# chainclock.net
KiCad netlist of a schematic drawn in EAGLE
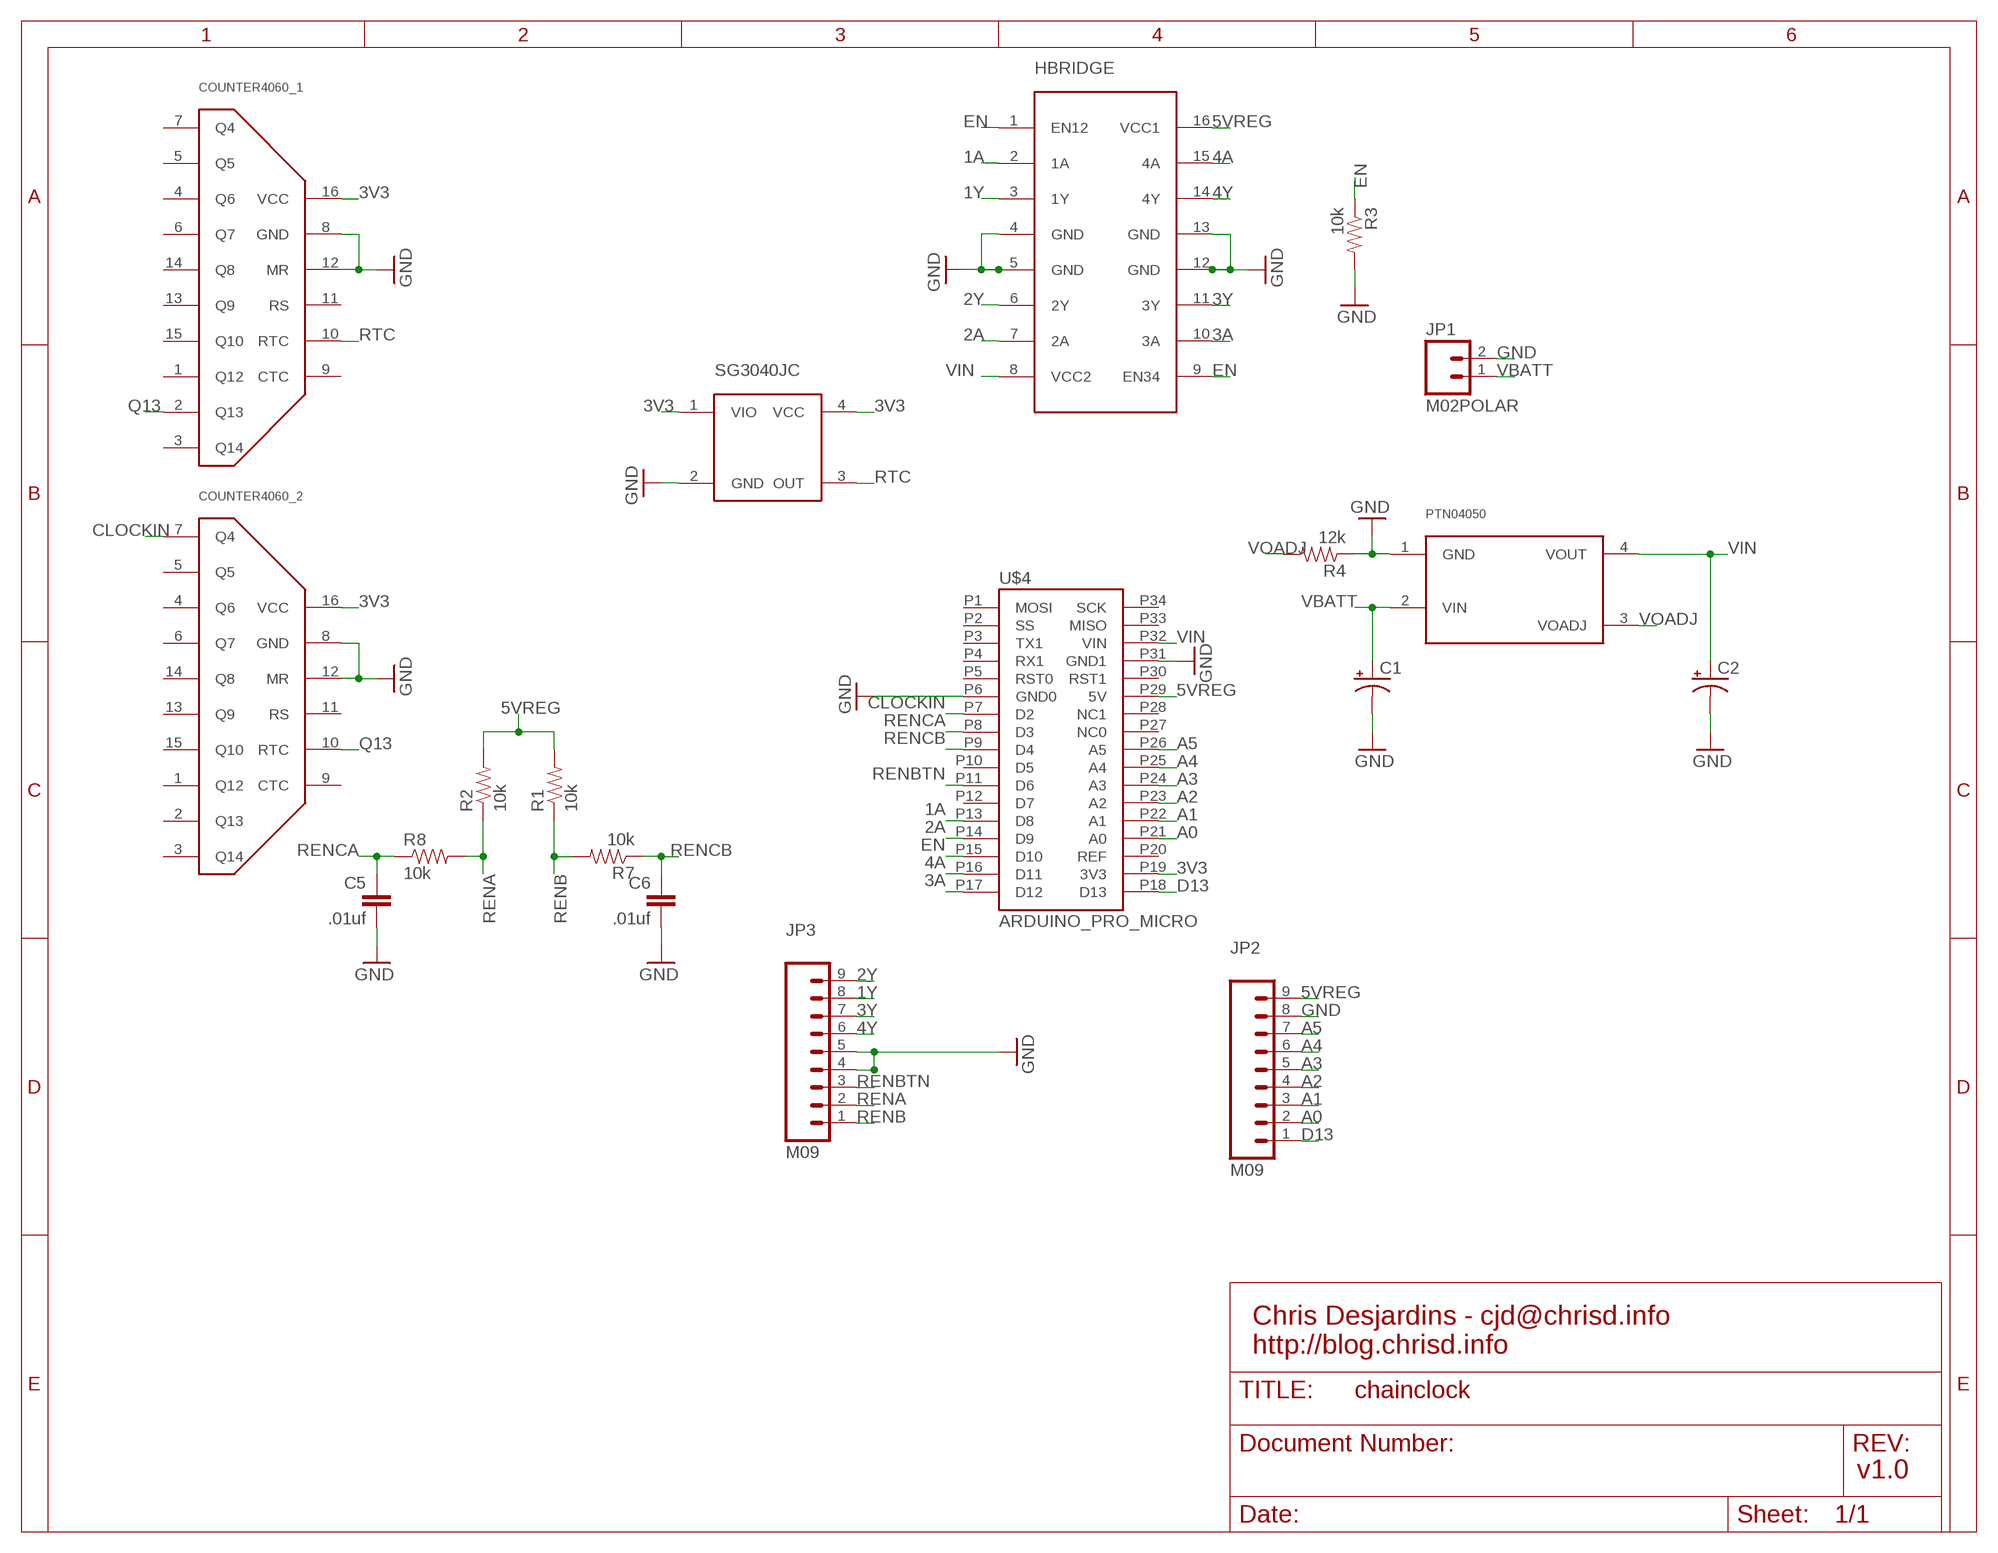
[diagram p0: schematic, sheet 1]

(export (version "E")
  (design (tool "Eeschema 10.0.6"))
  (components
    (comp (ref "C1")
      (value "CAP_POLPTH1")
      (footprint "eagle-import:CPOL-RADIAL-100UF-25V")
      (libsource (lib "eagle-import") (part "CAP_POLPTH1"))
    )
    (comp (ref "C2")
      (value "CAP_POLPTH1")
      (footprint "eagle-import:CPOL-RADIAL-100UF-25V")
      (libsource (lib "eagle-import") (part "CAP_POLPTH1"))
    )
    (comp (ref "C5")
      (value ".01uf")
      (footprint "eagle-import:CAP-PTH-SMALL-KIT")
      (libsource (lib "eagle-import") (part "CAPKIT"))
    )
    (comp (ref "C6")
      (value ".01uf")
      (footprint "eagle-import:CAP-PTH-SMALL-KIT")
      (libsource (lib "eagle-import") (part "CAPKIT"))
    )
    (comp (ref "COUNTER4060_1")
      (value "4060SOIC16")
      (footprint "eagle-import:SO016")
      (libsource (lib "eagle-import") (part "4060SOIC16"))
    )
    (comp (ref "COUNTER4060_2")
      (value "4060SOIC16")
      (footprint "eagle-import:SO016")
      (libsource (lib "eagle-import") (part "4060SOIC16"))
    )
    (comp (ref "HBRIDGE")
      (value "SN754410")
      (footprint "eagle-import:DIL16-KIT")
      (libsource (lib "eagle-import") (part "SN754410"))
    )
    (comp (ref "JP1")
      (value "M02POLAR")
      (footprint "eagle-import:MOLEX-1X2")
      (libsource (lib "eagle-import") (part "M02POLAR"))
    )
    (comp (ref "JP2")
      (value "M09")
      (footprint "eagle-import:1X09")
      (libsource (lib "eagle-import") (part "M09"))
    )
    (comp (ref "JP3")
      (value "M09")
      (footprint "eagle-import:1X09")
      (libsource (lib "eagle-import") (part "M09"))
    )
    (comp (ref "PTN04050")
      (value "PTN0405C")
      (footprint "eagle-import:EUU4")
      (libsource (lib "eagle-import") (part "PTN0405C"))
    )
    (comp (ref "R1")
      (value "10k")
      (footprint "eagle-import:AXIAL-0.3EZ")
      (libsource (lib "eagle-import") (part "RESISTOREZ"))
    )
    (comp (ref "R2")
      (value "10k")
      (footprint "eagle-import:AXIAL-0.3EZ")
      (libsource (lib "eagle-import") (part "RESISTOREZ"))
    )
    (comp (ref "R3")
      (value "10k")
      (footprint "eagle-import:AXIAL-0.3EZ")
      (libsource (lib "eagle-import") (part "RESISTOREZ"))
    )
    (comp (ref "R4")
      (value "12k")
      (footprint "eagle-import:AXIAL-0.3EZ")
      (libsource (lib "eagle-import") (part "RESISTOREZ"))
    )
    (comp (ref "R7")
      (value "10k")
      (footprint "eagle-import:AXIAL-0.3EZ")
      (libsource (lib "eagle-import") (part "RESISTOREZ"))
    )
    (comp (ref "R8")
      (value "10k")
      (footprint "eagle-import:AXIAL-0.3EZ")
      (libsource (lib "eagle-import") (part "RESISTOREZ"))
    )
    (comp (ref "SG3040JC")
      (value "SG30XXJC")
      (footprint "eagle-import:SG3030JC")
      (libsource (lib "eagle-import") (part "SG30XXJC"))
    )
    (comp (ref "U$4")
      (value "ARDUINO_PRO_MICRO")
      (footprint "eagle-import:ARDUINO_PRO_MICRO")
      (libsource (lib "eagle-import") (part "ARDUINO_PRO_MICRO"))
    )
  )
  (nets
    (net (code "1") (name "/1A") (class "Default")
      (node (ref "HBRIDGE") (pin "2") (pinfunction "1A_2") (pintype "bidirectional"))
      (node (ref "U$4") (pin "P13") (pinfunction "D8_P13") (pintype "bidirectional"))
    )
    (net (code "2") (name "/1Y") (class "Default")
      (node (ref "HBRIDGE") (pin "3") (pinfunction "1Y_3") (pintype "bidirectional"))
      (node (ref "JP3") (pin "8") (pinfunction "8_8") (pintype "passive"))
    )
    (net (code "3") (name "/2A") (class "Default")
      (node (ref "HBRIDGE") (pin "7") (pinfunction "2A_7") (pintype "bidirectional"))
      (node (ref "U$4") (pin "P14") (pinfunction "D9_P14") (pintype "bidirectional"))
    )
    (net (code "4") (name "/2Y") (class "Default")
      (node (ref "HBRIDGE") (pin "6") (pinfunction "2Y_6") (pintype "bidirectional"))
      (node (ref "JP3") (pin "9") (pinfunction "9_9") (pintype "passive"))
    )
    (net (code "5") (name "/3A") (class "Default")
      (node (ref "HBRIDGE") (pin "10") (pinfunction "3A_10") (pintype "bidirectional"))
      (node (ref "U$4") (pin "P17") (pinfunction "D12_P17") (pintype "bidirectional"))
    )
    (net (code "6") (name "/3V3") (class "Default")
      (node (ref "COUNTER4060_1") (pin "16") (pinfunction "VCC_16") (pintype "power_in"))
      (node (ref "COUNTER4060_2") (pin "16") (pinfunction "VCC_16") (pintype "power_in"))
      (node (ref "SG3040JC") (pin "1") (pinfunction "VIO_1") (pintype "power_in"))
      (node (ref "SG3040JC") (pin "4") (pinfunction "VCC_4") (pintype "power_in"))
      (node (ref "U$4") (pin "P19") (pinfunction "3V3_P19") (pintype "power_in"))
    )
    (net (code "7") (name "/3Y") (class "Default")
      (node (ref "HBRIDGE") (pin "11") (pinfunction "3Y_11") (pintype "bidirectional"))
      (node (ref "JP3") (pin "7") (pinfunction "7_7") (pintype "passive"))
    )
    (net (code "8") (name "/4A") (class "Default")
      (node (ref "HBRIDGE") (pin "15") (pinfunction "4A_15") (pintype "bidirectional"))
      (node (ref "U$4") (pin "P16") (pinfunction "D11_P16") (pintype "bidirectional"))
    )
    (net (code "9") (name "/4Y") (class "Default")
      (node (ref "HBRIDGE") (pin "14") (pinfunction "4Y_14") (pintype "bidirectional"))
      (node (ref "JP3") (pin "6") (pinfunction "6_6") (pintype "passive"))
    )
    (net (code "10") (name "/5VREG") (class "Default")
      (node (ref "HBRIDGE") (pin "16") (pinfunction "VCC1_16") (pintype "bidirectional"))
      (node (ref "JP2") (pin "9") (pinfunction "9_9") (pintype "passive"))
      (node (ref "R1") (pin "P$2") (pinfunction "2_P$2") (pintype "passive"))
      (node (ref "R2") (pin "P$2") (pinfunction "2_P$2") (pintype "passive"))
      (node (ref "U$4") (pin "P29") (pinfunction "5V_P29") (pintype "power_in"))
    )
    (net (code "11") (name "/A0") (class "Default")
      (node (ref "JP2") (pin "2") (pinfunction "2_2") (pintype "passive"))
      (node (ref "U$4") (pin "P21") (pinfunction "A0_P21") (pintype "bidirectional"))
    )
    (net (code "12") (name "/A1") (class "Default")
      (node (ref "JP2") (pin "3") (pinfunction "3_3") (pintype "passive"))
      (node (ref "U$4") (pin "P22") (pinfunction "A1_P22") (pintype "bidirectional"))
    )
    (net (code "13") (name "/A2") (class "Default")
      (node (ref "JP2") (pin "4") (pinfunction "4_4") (pintype "passive"))
      (node (ref "U$4") (pin "P23") (pinfunction "A2_P23") (pintype "bidirectional"))
    )
    (net (code "14") (name "/A3") (class "Default")
      (node (ref "JP2") (pin "5") (pinfunction "5_5") (pintype "passive"))
      (node (ref "U$4") (pin "P24") (pinfunction "A3_P24") (pintype "bidirectional"))
    )
    (net (code "15") (name "/A4") (class "Default")
      (node (ref "JP2") (pin "6") (pinfunction "6_6") (pintype "passive"))
      (node (ref "U$4") (pin "P25") (pinfunction "A4_P25") (pintype "bidirectional"))
    )
    (net (code "16") (name "/A5") (class "Default")
      (node (ref "JP2") (pin "7") (pinfunction "7_7") (pintype "passive"))
      (node (ref "U$4") (pin "P26") (pinfunction "A5_P26") (pintype "bidirectional"))
    )
    (net (code "17") (name "/CLOCKIN") (class "Default")
      (node (ref "COUNTER4060_2") (pin "7") (pinfunction "Q4_7") (pintype "bidirectional"))
      (node (ref "U$4") (pin "P7") (pinfunction "D2_P7") (pintype "bidirectional"))
    )
    (net (code "18") (name "/D13") (class "Default")
      (node (ref "JP2") (pin "1") (pinfunction "1_1") (pintype "passive"))
      (node (ref "U$4") (pin "P18") (pinfunction "D13_P18") (pintype "bidirectional"))
    )
    (net (code "19") (name "/EN") (class "Default")
      (node (ref "HBRIDGE") (pin "1") (pinfunction "EN12_1") (pintype "bidirectional"))
      (node (ref "HBRIDGE") (pin "9") (pinfunction "EN34_9") (pintype "bidirectional"))
      (node (ref "R3") (pin "P$1") (pinfunction "1_P$1") (pintype "passive"))
      (node (ref "U$4") (pin "P15") (pinfunction "D10_P15") (pintype "bidirectional"))
    )
    (net (code "20") (name "/Q13") (class "Default")
      (node (ref "COUNTER4060_1") (pin "2") (pinfunction "Q13_2") (pintype "bidirectional"))
      (node (ref "COUNTER4060_2") (pin "10") (pinfunction "RTC_10") (pintype "bidirectional"))
    )
    (net (code "21") (name "/REF") (class "Default")
      (node (ref "U$4") (pin "P20") (pinfunction "REF_P20") (pintype "power_in"))
    )
    (net (code "22") (name "/RENA") (class "Default")
      (node (ref "JP3") (pin "2") (pinfunction "2_2") (pintype "passive"))
      (node (ref "R2") (pin "P$1") (pinfunction "1_P$1") (pintype "passive"))
      (node (ref "R8") (pin "P$2") (pinfunction "2_P$2") (pintype "passive"))
    )
    (net (code "23") (name "/RENB") (class "Default")
      (node (ref "JP3") (pin "1") (pinfunction "1_1") (pintype "passive"))
      (node (ref "R1") (pin "P$1") (pinfunction "1_P$1") (pintype "passive"))
      (node (ref "R7") (pin "P$2") (pinfunction "2_P$2") (pintype "passive"))
    )
    (net (code "24") (name "/RENBTN") (class "Default")
      (node (ref "JP3") (pin "3") (pinfunction "3_3") (pintype "passive"))
      (node (ref "U$4") (pin "P11") (pinfunction "D6_P11") (pintype "bidirectional"))
    )
    (net (code "25") (name "/RENCA") (class "Default")
      (node (ref "C5") (pin "1") (pinfunction "1_1") (pintype "passive"))
      (node (ref "R8") (pin "P$1") (pinfunction "1_P$1") (pintype "passive"))
      (node (ref "U$4") (pin "P8") (pinfunction "D3_P8") (pintype "bidirectional"))
    )
    (net (code "26") (name "/RENCB") (class "Default")
      (node (ref "C6") (pin "1") (pinfunction "1_1") (pintype "passive"))
      (node (ref "R7") (pin "P$1") (pinfunction "1_P$1") (pintype "passive"))
      (node (ref "U$4") (pin "P9") (pinfunction "D4_P9") (pintype "bidirectional"))
    )
    (net (code "27") (name "/RTC") (class "Default")
      (node (ref "COUNTER4060_1") (pin "10") (pinfunction "RTC_10") (pintype "bidirectional"))
      (node (ref "SG3040JC") (pin "3") (pinfunction "OUT_3") (pintype "bidirectional"))
    )
    (net (code "28") (name "/VBATT") (class "Default")
      (node (ref "C1") (pin "1") (pinfunction "+_1") (pintype "passive"))
      (node (ref "JP1") (pin "1") (pinfunction "1_1") (pintype "passive"))
      (node (ref "PTN04050") (pin "2") (pinfunction "VIN_2") (pintype "power_in"))
    )
    (net (code "29") (name "/VIN") (class "Default")
      (node (ref "C2") (pin "1") (pinfunction "+_1") (pintype "passive"))
      (node (ref "HBRIDGE") (pin "8") (pinfunction "VCC2_8") (pintype "bidirectional"))
      (node (ref "PTN04050") (pin "4") (pinfunction "VOUT_4") (pintype "power_in"))
      (node (ref "U$4") (pin "P32") (pinfunction "VIN_P32") (pintype "power_in"))
    )
    (net (code "30") (name "/VOADJ") (class "Default")
      (node (ref "PTN04050") (pin "3") (pinfunction "VOADJ_3") (pintype "power_in"))
      (node (ref "R4") (pin "P$2") (pinfunction "2_P$2") (pintype "passive"))
    )
    (net (code "31") (name "GND") (class "Default")
      (node (ref "C1") (pin "2") (pinfunction "-_2") (pintype "passive"))
      (node (ref "C2") (pin "2") (pinfunction "-_2") (pintype "passive"))
      (node (ref "C5") (pin "2") (pinfunction "2_2") (pintype "passive"))
      (node (ref "C6") (pin "2") (pinfunction "2_2") (pintype "passive"))
      (node (ref "COUNTER4060_1") (pin "12") (pinfunction "MR_12") (pintype "bidirectional"))
      (node (ref "COUNTER4060_1") (pin "8") (pinfunction "GND_8") (pintype "power_in"))
      (node (ref "COUNTER4060_2") (pin "12") (pinfunction "MR_12") (pintype "bidirectional"))
      (node (ref "COUNTER4060_2") (pin "8") (pinfunction "GND_8") (pintype "power_in"))
      (node (ref "HBRIDGE") (pin "12") (pinfunction "GND_12") (pintype "bidirectional"))
      (node (ref "HBRIDGE") (pin "13") (pinfunction "GND_13") (pintype "bidirectional"))
      (node (ref "HBRIDGE") (pin "4") (pinfunction "GND_4") (pintype "bidirectional"))
      (node (ref "HBRIDGE") (pin "5") (pinfunction "GND_5") (pintype "bidirectional"))
      (node (ref "JP1") (pin "2") (pinfunction "2_2") (pintype "passive"))
      (node (ref "JP2") (pin "8") (pinfunction "8_8") (pintype "passive"))
      (node (ref "JP3") (pin "4") (pinfunction "4_4") (pintype "passive"))
      (node (ref "JP3") (pin "5") (pinfunction "5_5") (pintype "passive"))
      (node (ref "PTN04050") (pin "1") (pinfunction "GND_1") (pintype "power_in"))
      (node (ref "R3") (pin "P$2") (pinfunction "2_P$2") (pintype "passive"))
      (node (ref "R4") (pin "P$1") (pinfunction "1_P$1") (pintype "passive"))
      (node (ref "SG3040JC") (pin "2") (pinfunction "GND_2") (pintype "power_in"))
      (node (ref "U$4") (pin "P31") (pinfunction "GND1_P31") (pintype "power_in"))
      (node (ref "U$4") (pin "P6") (pinfunction "GND0_P6") (pintype "power_in"))
    )
    (net (code "32") (name "unconnected-(COUNTER4060_1-CTC-Pad9)") (class "Default")
      (node (ref "COUNTER4060_1") (pin "9") (pinfunction "CTC_9") (pintype "bidirectional"))
    )
    (net (code "33") (name "unconnected-(COUNTER4060_1-Q4-Pad7)") (class "Default")
      (node (ref "COUNTER4060_1") (pin "7") (pinfunction "Q4_7") (pintype "bidirectional"))
    )
    (net (code "34") (name "unconnected-(COUNTER4060_1-Q5-Pad5)") (class "Default")
      (node (ref "COUNTER4060_1") (pin "5") (pinfunction "Q5_5") (pintype "bidirectional"))
    )
    (net (code "35") (name "unconnected-(COUNTER4060_1-Q6-Pad4)") (class "Default")
      (node (ref "COUNTER4060_1") (pin "4") (pinfunction "Q6_4") (pintype "bidirectional"))
    )
    (net (code "36") (name "unconnected-(COUNTER4060_1-Q7-Pad6)") (class "Default")
      (node (ref "COUNTER4060_1") (pin "6") (pinfunction "Q7_6") (pintype "bidirectional"))
    )
    (net (code "37") (name "unconnected-(COUNTER4060_1-Q8-Pad14)") (class "Default")
      (node (ref "COUNTER4060_1") (pin "14") (pinfunction "Q8_14") (pintype "bidirectional"))
    )
    (net (code "38") (name "unconnected-(COUNTER4060_1-Q9-Pad13)") (class "Default")
      (node (ref "COUNTER4060_1") (pin "13") (pinfunction "Q9_13") (pintype "bidirectional"))
    )
    (net (code "39") (name "unconnected-(COUNTER4060_1-Q10-Pad15)") (class "Default")
      (node (ref "COUNTER4060_1") (pin "15") (pinfunction "Q10_15") (pintype "bidirectional"))
    )
    (net (code "40") (name "unconnected-(COUNTER4060_1-Q12-Pad1)") (class "Default")
      (node (ref "COUNTER4060_1") (pin "1") (pinfunction "Q12_1") (pintype "bidirectional"))
    )
    (net (code "41") (name "unconnected-(COUNTER4060_1-Q14-Pad3)") (class "Default")
      (node (ref "COUNTER4060_1") (pin "3") (pinfunction "Q14_3") (pintype "bidirectional"))
    )
    (net (code "42") (name "unconnected-(COUNTER4060_1-RS-Pad11)") (class "Default")
      (node (ref "COUNTER4060_1") (pin "11") (pinfunction "RS_11") (pintype "bidirectional"))
    )
    (net (code "43") (name "unconnected-(COUNTER4060_2-CTC-Pad9)") (class "Default")
      (node (ref "COUNTER4060_2") (pin "9") (pinfunction "CTC_9") (pintype "bidirectional"))
    )
    (net (code "44") (name "unconnected-(COUNTER4060_2-Q5-Pad5)") (class "Default")
      (node (ref "COUNTER4060_2") (pin "5") (pinfunction "Q5_5") (pintype "bidirectional"))
    )
    (net (code "45") (name "unconnected-(COUNTER4060_2-Q6-Pad4)") (class "Default")
      (node (ref "COUNTER4060_2") (pin "4") (pinfunction "Q6_4") (pintype "bidirectional"))
    )
    (net (code "46") (name "unconnected-(COUNTER4060_2-Q7-Pad6)") (class "Default")
      (node (ref "COUNTER4060_2") (pin "6") (pinfunction "Q7_6") (pintype "bidirectional"))
    )
    (net (code "47") (name "unconnected-(COUNTER4060_2-Q8-Pad14)") (class "Default")
      (node (ref "COUNTER4060_2") (pin "14") (pinfunction "Q8_14") (pintype "bidirectional"))
    )
    (net (code "48") (name "unconnected-(COUNTER4060_2-Q9-Pad13)") (class "Default")
      (node (ref "COUNTER4060_2") (pin "13") (pinfunction "Q9_13") (pintype "bidirectional"))
    )
    (net (code "49") (name "unconnected-(COUNTER4060_2-Q10-Pad15)") (class "Default")
      (node (ref "COUNTER4060_2") (pin "15") (pinfunction "Q10_15") (pintype "bidirectional"))
    )
    (net (code "50") (name "unconnected-(COUNTER4060_2-Q12-Pad1)") (class "Default")
      (node (ref "COUNTER4060_2") (pin "1") (pinfunction "Q12_1") (pintype "bidirectional"))
    )
    (net (code "51") (name "unconnected-(COUNTER4060_2-Q13-Pad2)") (class "Default")
      (node (ref "COUNTER4060_2") (pin "2") (pinfunction "Q13_2") (pintype "bidirectional"))
    )
    (net (code "52") (name "unconnected-(COUNTER4060_2-Q14-Pad3)") (class "Default")
      (node (ref "COUNTER4060_2") (pin "3") (pinfunction "Q14_3") (pintype "bidirectional"))
    )
    (net (code "53") (name "unconnected-(COUNTER4060_2-RS-Pad11)") (class "Default")
      (node (ref "COUNTER4060_2") (pin "11") (pinfunction "RS_11") (pintype "bidirectional"))
    )
    (net (code "54") (name "unconnected-(U$4-D5-PadP10)") (class "Default")
      (node (ref "U$4") (pin "P10") (pinfunction "D5_P10") (pintype "bidirectional"))
    )
    (net (code "55") (name "unconnected-(U$4-D7-PadP12)") (class "Default")
      (node (ref "U$4") (pin "P12") (pinfunction "D7_P12") (pintype "bidirectional"))
    )
    (net (code "56") (name "unconnected-(U$4-MISO-PadP33)") (class "Default")
      (node (ref "U$4") (pin "P33") (pinfunction "MISO_P33") (pintype "bidirectional"))
    )
    (net (code "57") (name "unconnected-(U$4-MOSI-PadP1)") (class "Default")
      (node (ref "U$4") (pin "P1") (pinfunction "MOSI_P1") (pintype "bidirectional"))
    )
    (net (code "58") (name "unconnected-(U$4-NC0-PadP27)") (class "Default")
      (node (ref "U$4") (pin "P27") (pinfunction "NC0_P27") (pintype "no_connect"))
    )
    (net (code "59") (name "unconnected-(U$4-NC1-PadP28)") (class "Default")
      (node (ref "U$4") (pin "P28") (pinfunction "NC1_P28") (pintype "no_connect"))
    )
    (net (code "60") (name "unconnected-(U$4-RST0-PadP5)") (class "Default")
      (node (ref "U$4") (pin "P5") (pinfunction "RST0_P5") (pintype "bidirectional"))
    )
    (net (code "61") (name "unconnected-(U$4-RST1-PadP30)") (class "Default")
      (node (ref "U$4") (pin "P30") (pinfunction "RST1_P30") (pintype "bidirectional"))
    )
    (net (code "62") (name "unconnected-(U$4-RX1-PadP4)") (class "Default")
      (node (ref "U$4") (pin "P4") (pinfunction "RX1_P4") (pintype "bidirectional"))
    )
    (net (code "63") (name "unconnected-(U$4-SCK-PadP34)") (class "Default")
      (node (ref "U$4") (pin "P34") (pinfunction "SCK_P34") (pintype "bidirectional"))
    )
    (net (code "64") (name "unconnected-(U$4-SS-PadP2)") (class "Default")
      (node (ref "U$4") (pin "P2") (pinfunction "SS_P2") (pintype "bidirectional"))
    )
    (net (code "65") (name "unconnected-(U$4-TX1-PadP3)") (class "Default")
      (node (ref "U$4") (pin "P3") (pinfunction "TX1_P3") (pintype "bidirectional"))
    )
  )
)
